# double_sece.net
KiCad netlist of a schematic drawn in Altium Designer
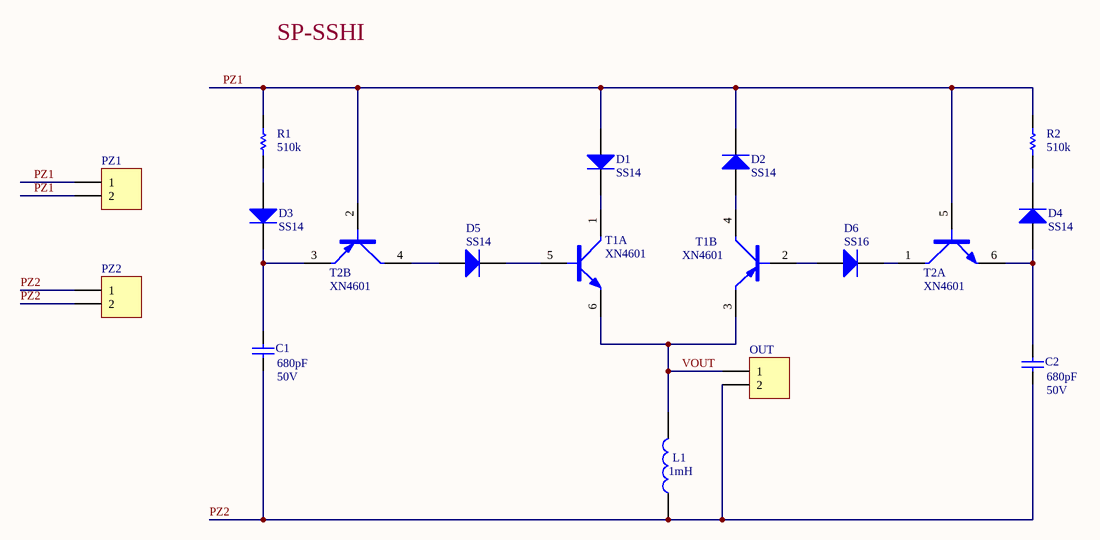
[diagram p0: double_sece.SchDoc]

(export (version "E")
  (design (tool "Eeschema 10.0.6"))
  (components
    (comp (ref "C1")
      (value "680pF")
      (footprint "6-0805_N")
      (description "Capacitor")
      (fields
        (field (name "NOMINAL VOLTAGE") "50V")
        (field (name "Comment") "CAP")
        (field (name "PUBLISHER") "Altium Limited")
      )
      (libsource (lib "Harry_PCBLib") (part "Cap"))
    )
    (comp (ref "C2")
      (value "680pF")
      (footprint "6-0805_N")
      (description "Capacitor")
      (fields
        (field (name "NOMINAL VOLTAGE") "50V")
        (field (name "Comment") "CAP")
        (field (name "PUBLISHER") "Altium Limited")
      )
      (libsource (lib "Harry_PCBLib") (part "Cap"))
    )
    (comp (ref "D1")
      (value "SS14")
      (footprint "SMD SS16")
      (description "1 Amp General Purpose Rectifier")
      (fields (field (name "PUBLISHER") "Altium Limited"))
      (libsource (lib "Miscellaneous Devices") (part "Diode 1N4004"))
    )
    (comp (ref "D2")
      (value "SS14")
      (footprint "SMD SS16")
      (description "1 Amp General Purpose Rectifier")
      (fields (field (name "PUBLISHER") "Altium Limited"))
      (libsource (lib "Miscellaneous Devices") (part "Diode 1N4004"))
    )
    (comp (ref "D3")
      (value "SS14")
      (footprint "SMD SS16")
      (description "1 Amp General Purpose Rectifier")
      (fields (field (name "PUBLISHER") "Altium Limited"))
      (libsource (lib "Miscellaneous Devices") (part "Diode 1N4004"))
    )
    (comp (ref "D4")
      (value "SS14")
      (footprint "SMD SS16")
      (description "1 Amp General Purpose Rectifier")
      (fields (field (name "PUBLISHER") "Altium Limited"))
      (libsource (lib "Miscellaneous Devices") (part "Diode 1N4004"))
    )
    (comp (ref "D5")
      (value "SS14")
      (footprint "SMD SS16")
      (description "1 Amp General Purpose Rectifier")
      (fields (field (name "PUBLISHER") "Altium Limited"))
      (libsource (lib "Miscellaneous Devices") (part "Diode 1N4004"))
    )
    (comp (ref "D6")
      (value "SS16")
      (footprint "SMD SS16")
      (description "1 Amp General Purpose Rectifier")
      (fields (field (name "PUBLISHER") "Altium Limited"))
      (libsource (lib "Miscellaneous Devices") (part "Diode 1N4004"))
    )
    (comp (ref "L1") (value "1mH") (footprint "1812") (libsource (lib "Harry_PCBLib") (part "INDUCTOR")))
    (comp (ref "OUT")
      (value "Header 2")
      (footprint "HDR1X2")
      (description "Header, 2-Pin")
      (fields (field (name "PUBLISHER") "Altium Limited"))
      (libsource (lib "Miscellaneous Connectors") (part "Header 2"))
    )
    (comp (ref "PZ1")
      (value "Header 2")
      (footprint "HDR1X2")
      (description "Header, 2-Pin")
      (fields (field (name "PUBLISHER") "Altium Limited"))
      (libsource (lib "Miscellaneous Connectors") (part "Header 2"))
    )
    (comp (ref "PZ2")
      (value "Header 2")
      (footprint "HDR1X2")
      (description "Header, 2-Pin")
      (fields (field (name "PUBLISHER") "Altium Limited"))
      (libsource (lib "Miscellaneous Connectors") (part "Header 2"))
    )
    (comp (ref "R1")
      (value "510k")
      (footprint "6-0805_N")
      (description "Resistor")
      (fields (field (name "Comment") "Res1") (field (name "PUBLISHER") "Altium Limited"))
      (libsource (lib "Miscellaneous Devices") (part "Res1"))
    )
    (comp (ref "R2")
      (value "510k")
      (footprint "6-0805_N")
      (description "Resistor")
      (fields (field (name "Comment") "Res1") (field (name "PUBLISHER") "Altium Limited"))
      (libsource (lib "Miscellaneous Devices") (part "Res1"))
    )
    (comp (ref "T1")
      (value "XN4601")
      (footprint "XN4601")
      (description "Composite Transistors")
      (libsource (lib "Self-power SSHI") (part "XN4601"))
    )
    (comp (ref "T2")
      (value "XN4601")
      (footprint "XN4601")
      (description "Composite Transistors")
      (libsource (lib "Self-power SSHI") (part "XN4601"))
    )
  )
  (nets
    (net (code "1") (name "/PZ1") (class "Default")
      (node (ref "D1") (pin "1") (pinfunction "A_1") (pintype "passive"))
      (node (ref "D2") (pin "2") (pinfunction "K_2") (pintype "passive"))
      (node (ref "PZ1") (pin "1") (pinfunction "1_1") (pintype "passive"))
      (node (ref "PZ1") (pin "2") (pinfunction "2_2") (pintype "passive"))
      (node (ref "R1") (pin "2") (pinfunction "2_2") (pintype "passive"))
      (node (ref "R2") (pin "2") (pinfunction "2_2") (pintype "passive"))
      (node (ref "T2") (pin "2") (pinfunction "PNP_B_2") (pintype "passive"))
      (node (ref "T2") (pin "5") (pinfunction "NPN_B_5") (pintype "passive"))
    )
    (net (code "2") (name "/PZ2") (class "Default")
      (node (ref "C1") (pin "1") (pinfunction "1_1") (pintype "passive"))
      (node (ref "C2") (pin "1") (pinfunction "1_1") (pintype "passive"))
      (node (ref "L1") (pin "1") (pinfunction "1_1") (pintype "passive"))
      (node (ref "OUT") (pin "2") (pinfunction "2_2") (pintype "passive"))
      (node (ref "PZ2") (pin "1") (pinfunction "1_1") (pintype "passive"))
      (node (ref "PZ2") (pin "2") (pinfunction "2_2") (pintype "passive"))
    )
    (net (code "3") (name "/VOUT") (class "Default")
      (node (ref "L1") (pin "2") (pinfunction "2_2") (pintype "passive"))
      (node (ref "OUT") (pin "1") (pinfunction "1_1") (pintype "passive"))
      (node (ref "T1") (pin "3") (pinfunction "PNP_E_3") (pintype "passive"))
      (node (ref "T1") (pin "6") (pinfunction "NPN_E_6") (pintype "passive"))
    )
    (net (code "4") (name "Net-(D1-K)") (class "Default")
      (node (ref "D1") (pin "2") (pinfunction "K_2") (pintype "passive"))
      (node (ref "T1") (pin "1") (pinfunction "NPN_C_1") (pintype "passive"))
    )
    (net (code "5") (name "Net-(D2-A)") (class "Default")
      (node (ref "D2") (pin "1") (pinfunction "A_1") (pintype "passive"))
      (node (ref "T1") (pin "4") (pinfunction "PNP_C_4") (pintype "passive"))
    )
    (net (code "6") (name "Net-(D3-A)") (class "Default")
      (node (ref "D3") (pin "1") (pinfunction "A_1") (pintype "passive"))
      (node (ref "R1") (pin "1") (pinfunction "1_1") (pintype "passive"))
    )
    (net (code "7") (name "Net-(D3-K)") (class "Default")
      (node (ref "C1") (pin "2") (pinfunction "2_2") (pintype "passive"))
      (node (ref "D3") (pin "2") (pinfunction "K_2") (pintype "passive"))
      (node (ref "T2") (pin "3") (pinfunction "PNP_E_3") (pintype "passive"))
    )
    (net (code "8") (name "Net-(D4-A)") (class "Default")
      (node (ref "C2") (pin "2") (pinfunction "2_2") (pintype "passive"))
      (node (ref "D4") (pin "1") (pinfunction "A_1") (pintype "passive"))
      (node (ref "T2") (pin "6") (pinfunction "NPN_E_6") (pintype "passive"))
    )
    (net (code "9") (name "Net-(D4-K)") (class "Default")
      (node (ref "D4") (pin "2") (pinfunction "K_2") (pintype "passive"))
      (node (ref "R2") (pin "1") (pinfunction "1_1") (pintype "passive"))
    )
    (net (code "10") (name "Net-(D5-A)") (class "Default")
      (node (ref "D5") (pin "1") (pinfunction "A_1") (pintype "passive"))
      (node (ref "T2") (pin "4") (pinfunction "PNP_C_4") (pintype "passive"))
    )
    (net (code "11") (name "Net-(D5-K)") (class "Default")
      (node (ref "D5") (pin "2") (pinfunction "K_2") (pintype "passive"))
      (node (ref "T1") (pin "5") (pinfunction "NPN_B_5") (pintype "passive"))
    )
    (net (code "12") (name "Net-(D6-A)") (class "Default")
      (node (ref "D6") (pin "1") (pinfunction "A_1") (pintype "passive"))
      (node (ref "T1") (pin "2") (pinfunction "PNP_B_2") (pintype "passive"))
    )
    (net (code "13") (name "Net-(D6-K)") (class "Default")
      (node (ref "D6") (pin "2") (pinfunction "K_2") (pintype "passive"))
      (node (ref "T2") (pin "1") (pinfunction "NPN_C_1") (pintype "passive"))
    )
  )
)
